# base.net
KiCad netlist of a schematic drawn in EAGLE
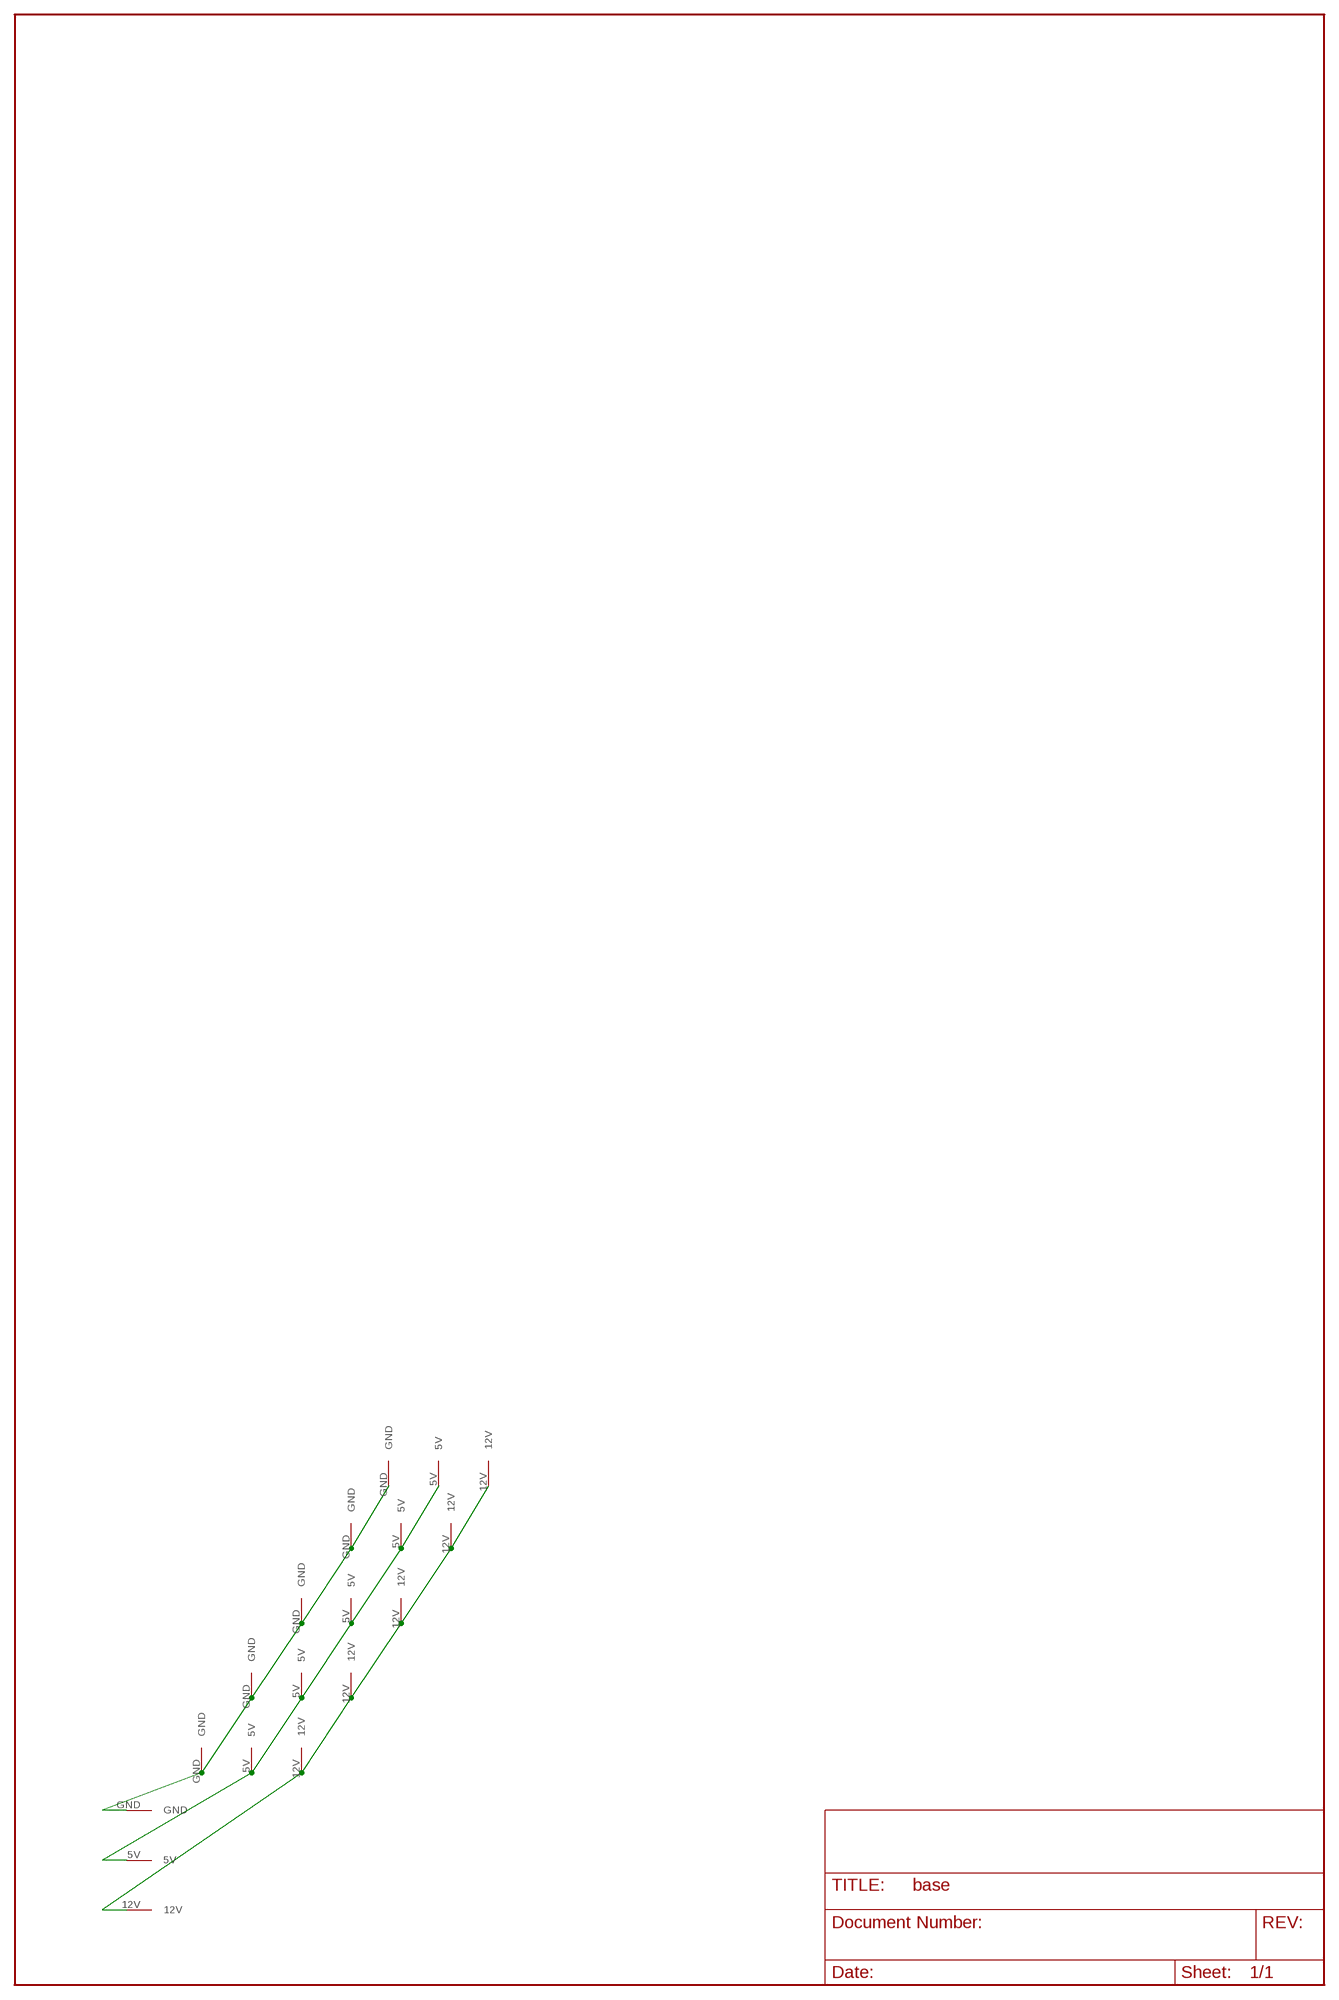
[diagram p0: schematic, sheet 1]

(export (version "E")
  (design (tool "Eeschema 10.0.6"))
  (components
    (comp (ref "U$1")
      (value "3POLE")
      (footprint "eagle-import:ARC2")
      (libsource (lib "eagle-import") (part "3POLE"))
    )
    (comp (ref "U$2")
      (value "3POLE")
      (footprint "eagle-import:ARC2")
      (libsource (lib "eagle-import") (part "3POLE"))
    )
    (comp (ref "U$3")
      (value "3POLE")
      (footprint "eagle-import:ARC2")
      (libsource (lib "eagle-import") (part "3POLE"))
    )
    (comp (ref "U$4")
      (value "3POLE")
      (footprint "eagle-import:ARC2")
      (libsource (lib "eagle-import") (part "3POLE"))
    )
    (comp (ref "U$5")
      (value "3POLE")
      (footprint "eagle-import:ARC2")
      (libsource (lib "eagle-import") (part "3POLE"))
    )
    (comp (ref "U$6")
      (value "3POLE")
      (footprint "eagle-import:ARC2")
      (libsource (lib "eagle-import") (part "3POLE"))
    )
  )
  (nets
    (net (code "1") (name "Net-(U$1-Pad5V)") (class "Default")
      (node (ref "U$1") (pin "5V") (pinfunction "5V_5V") (pintype "bidirectional"))
      (node (ref "U$2") (pin "5V") (pinfunction "5V_5V") (pintype "bidirectional"))
      (node (ref "U$3") (pin "5V") (pinfunction "5V_5V") (pintype "bidirectional"))
      (node (ref "U$4") (pin "5V") (pinfunction "5V_5V") (pintype "bidirectional"))
      (node (ref "U$5") (pin "5V") (pinfunction "5V_5V") (pintype "bidirectional"))
      (node (ref "U$6") (pin "5V") (pinfunction "5V_5V") (pintype "bidirectional"))
    )
    (net (code "2") (name "Net-(U$1-Pad12V)") (class "Default")
      (node (ref "U$1") (pin "12V") (pinfunction "12V_12V") (pintype "bidirectional"))
      (node (ref "U$2") (pin "12V") (pinfunction "12V_12V") (pintype "bidirectional"))
      (node (ref "U$3") (pin "12V") (pinfunction "12V_12V") (pintype "bidirectional"))
      (node (ref "U$4") (pin "12V") (pinfunction "12V_12V") (pintype "bidirectional"))
      (node (ref "U$5") (pin "12V") (pinfunction "12V_12V") (pintype "bidirectional"))
      (node (ref "U$6") (pin "12V") (pinfunction "12V_12V") (pintype "bidirectional"))
    )
    (net (code "3") (name "Net-(U$1-PadGND)") (class "Default")
      (node (ref "U$1") (pin "GND") (pinfunction "GND_GND") (pintype "bidirectional"))
      (node (ref "U$2") (pin "GND") (pinfunction "GND_GND") (pintype "bidirectional"))
      (node (ref "U$3") (pin "GND") (pinfunction "GND_GND") (pintype "bidirectional"))
      (node (ref "U$4") (pin "GND") (pinfunction "GND_GND") (pintype "bidirectional"))
      (node (ref "U$5") (pin "GND") (pinfunction "GND_GND") (pintype "bidirectional"))
      (node (ref "U$6") (pin "GND") (pinfunction "GND_GND") (pintype "bidirectional"))
    )
  )
)
